# blocking.net
KiCad netlist of a schematic drawn in Altium Designer
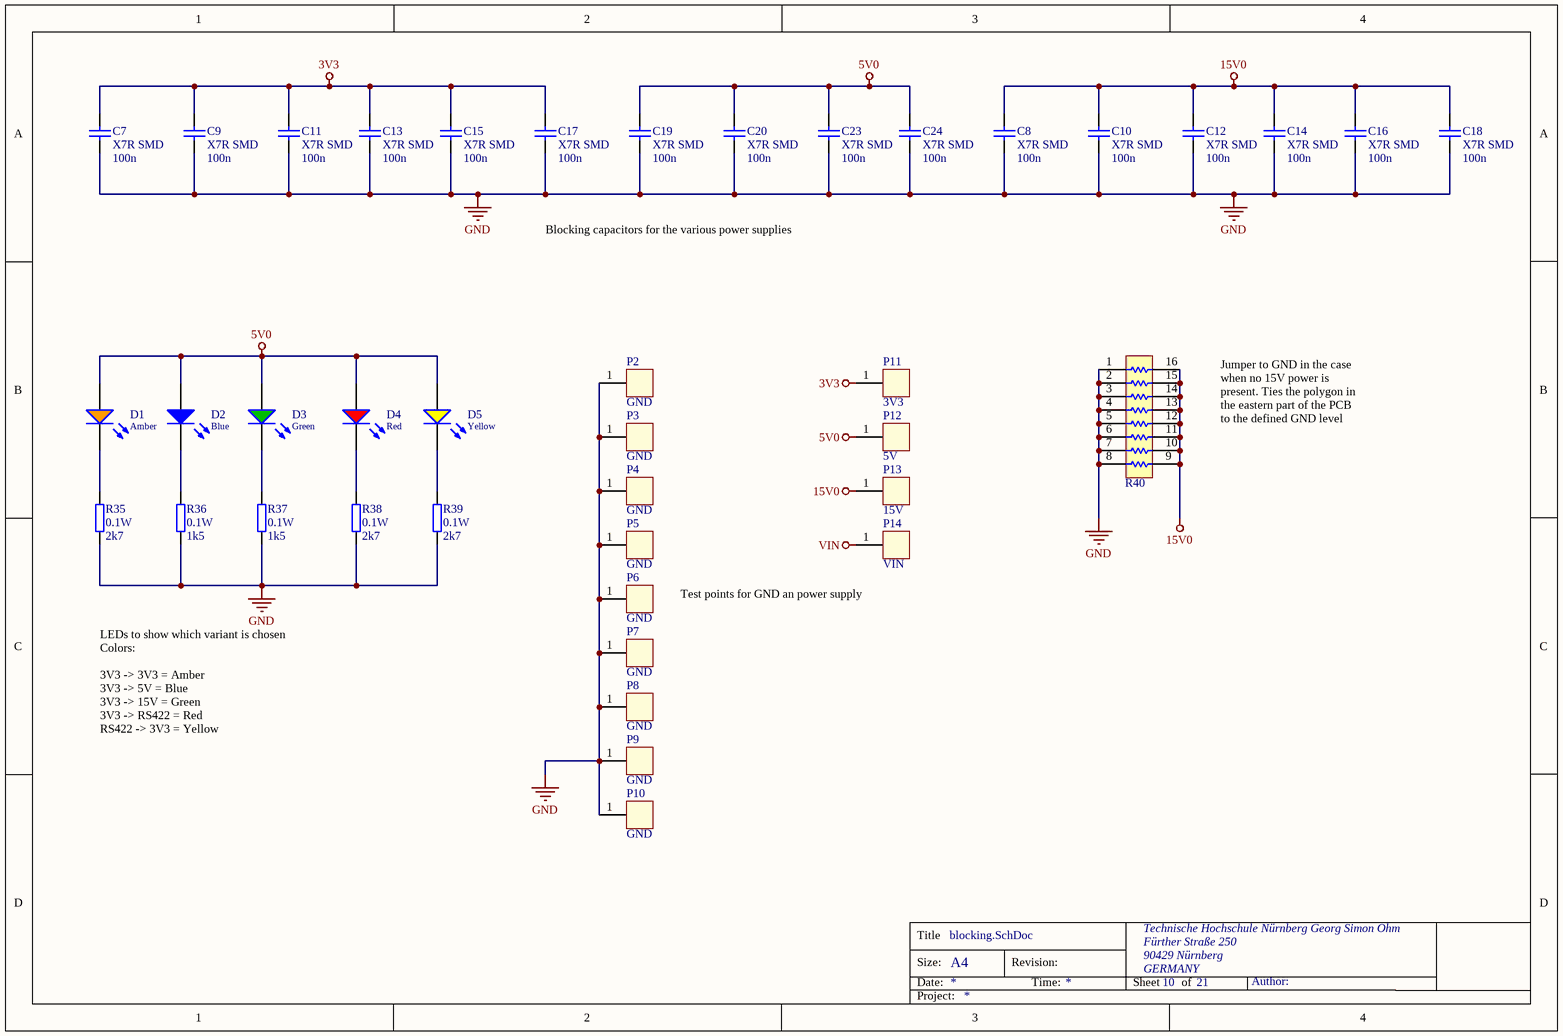
[diagram p0: blocking.SchDoc]

(export (version "E")
  (design (tool "Eeschema 10.0.6"))
  (components
    (comp (ref "C7")
      (value "X7R SMD")
      (footprint "CAPC3216X180X50ML20T25")
      (fields (field (name "ALTIUM_VALUE") "100n") (field (name "CREATED") "2019-12-08_Thilo_Wendt"))
      (libsource (lib "standard_rlc") (part "C_X7R_MEDIUM"))
    )
    (comp (ref "C8")
      (value "X7R SMD")
      (footprint "CAPC3216X180X50ML20T25")
      (fields (field (name "ALTIUM_VALUE") "100n") (field (name "CREATED") "2019-12-08_Thilo_Wendt"))
      (libsource (lib "standard_rlc") (part "C_X7R_MEDIUM"))
    )
    (comp (ref "C9")
      (value "X7R SMD")
      (footprint "CAPC3216X180X50ML20T25")
      (fields (field (name "ALTIUM_VALUE") "100n") (field (name "CREATED") "2019-12-08_Thilo_Wendt"))
      (libsource (lib "standard_rlc") (part "C_X7R_MEDIUM"))
    )
    (comp (ref "C10")
      (value "X7R SMD")
      (footprint "CAPC3216X180X50ML20T25")
      (fields (field (name "ALTIUM_VALUE") "100n") (field (name "CREATED") "2019-12-08_Thilo_Wendt"))
      (libsource (lib "standard_rlc") (part "C_X7R_MEDIUM"))
    )
    (comp (ref "C11")
      (value "X7R SMD")
      (footprint "CAPC3216X180X50ML20T25")
      (fields (field (name "ALTIUM_VALUE") "100n") (field (name "CREATED") "2019-12-08_Thilo_Wendt"))
      (libsource (lib "standard_rlc") (part "C_X7R_MEDIUM"))
    )
    (comp (ref "C12")
      (value "X7R SMD")
      (footprint "CAPC3216X180X50ML20T25")
      (fields (field (name "ALTIUM_VALUE") "100n") (field (name "CREATED") "2019-12-08_Thilo_Wendt"))
      (libsource (lib "standard_rlc") (part "C_X7R_MEDIUM"))
    )
    (comp (ref "C13")
      (value "X7R SMD")
      (footprint "CAPC3216X180X50ML20T25")
      (fields (field (name "ALTIUM_VALUE") "100n") (field (name "CREATED") "2019-12-08_Thilo_Wendt"))
      (libsource (lib "standard_rlc") (part "C_X7R_MEDIUM"))
    )
    (comp (ref "C14")
      (value "X7R SMD")
      (footprint "CAPC3216X180X50ML20T25")
      (fields (field (name "ALTIUM_VALUE") "100n") (field (name "CREATED") "2019-12-08_Thilo_Wendt"))
      (libsource (lib "standard_rlc") (part "C_X7R_MEDIUM"))
    )
    (comp (ref "C15")
      (value "X7R SMD")
      (footprint "CAPC3216X180X50ML20T25")
      (fields (field (name "ALTIUM_VALUE") "100n") (field (name "CREATED") "2019-12-08_Thilo_Wendt"))
      (libsource (lib "standard_rlc") (part "C_X7R_MEDIUM"))
    )
    (comp (ref "C16")
      (value "X7R SMD")
      (footprint "CAPC3216X180X50ML20T25")
      (fields (field (name "ALTIUM_VALUE") "100n") (field (name "CREATED") "2019-12-08_Thilo_Wendt"))
      (libsource (lib "standard_rlc") (part "C_X7R_MEDIUM"))
    )
    (comp (ref "C17")
      (value "X7R SMD")
      (footprint "CAPC3216X180X50ML20T25")
      (fields (field (name "ALTIUM_VALUE") "100n") (field (name "CREATED") "2019-12-08_Thilo_Wendt"))
      (libsource (lib "standard_rlc") (part "C_X7R_MEDIUM"))
    )
    (comp (ref "C18")
      (value "X7R SMD")
      (footprint "CAPC3216X180X50ML20T25")
      (fields (field (name "ALTIUM_VALUE") "100n") (field (name "CREATED") "2019-12-08_Thilo_Wendt"))
      (libsource (lib "standard_rlc") (part "C_X7R_MEDIUM"))
    )
    (comp (ref "C19")
      (value "X7R SMD")
      (footprint "CAPC3216X180X50ML20T25")
      (fields (field (name "ALTIUM_VALUE") "100n") (field (name "CREATED") "2019-12-08_Thilo_Wendt"))
      (libsource (lib "standard_rlc") (part "C_X7R_MEDIUM"))
    )
    (comp (ref "C20")
      (value "X7R SMD")
      (footprint "CAPC3216X180X50ML20T25")
      (fields (field (name "ALTIUM_VALUE") "100n") (field (name "CREATED") "2019-12-08_Thilo_Wendt"))
      (libsource (lib "standard_rlc") (part "C_X7R_MEDIUM"))
    )
    (comp (ref "C23")
      (value "X7R SMD")
      (footprint "CAPC3216X180X50ML20T25")
      (fields (field (name "ALTIUM_VALUE") "100n") (field (name "CREATED") "2019-12-08_Thilo_Wendt"))
      (libsource (lib "standard_rlc") (part "C_X7R_MEDIUM"))
    )
    (comp (ref "C24")
      (value "X7R SMD")
      (footprint "CAPC3216X180X50ML20T25")
      (fields (field (name "ALTIUM_VALUE") "100n") (field (name "CREATED") "2019-12-08_Thilo_Wendt"))
      (libsource (lib "standard_rlc") (part "C_X7R_MEDIUM"))
    )
    (comp (ref "D1")
      (value "Amber")
      (footprint "WL-SMCW_0603")
      (description "WL-SMCW SMD Mono-color Chip LED Waterclear, size 0603, Red, 2 V, 140°")
      (fields (field (name "EMITTING COLOR") "Amber") (field (name "CREATED") "2020-01-07_Thilo_Wendt"))
      (libsource (lib "optoelectronics") (part "LED_Amber"))
    )
    (comp (ref "D2")
      (value "Blue")
      (footprint "WL-SMCW_0603")
      (description "WL-SMCW SMD Mono-color Chip LED Waterclear, size 0603, Blue, 3.2 V, 140°")
      (fields
        (field (name "MPN") "150060BS75000")
        (field (name "MF") "Wuerth Elektronik")
        (field (name "EMITTING COLOR") "Blue")
        (field (name "CREATED") "2018_09_06_AGeiger")
      )
      (libsource (lib "optoelectronics") (part "LED_Blue"))
    )
    (comp (ref "D3")
      (value "Green")
      (footprint "WL-SMCW_0603")
      (description "WL-SMCW SMD Mono-color Chip LED Waterclear, size 0603, Green, 3.2 V, 140°")
      (fields
        (field (name "MPN") "150060GS75000")
        (field (name "MF") "Wuerth Elektronik")
        (field (name "EMITTING COLOR") "Green")
        (field (name "CREATED") "2018_09_06_AGeiger")
      )
      (libsource (lib "optoelectronics") (part "LED_Green"))
    )
    (comp (ref "D4")
      (value "Red")
      (footprint "WL-SMCW_0603")
      (description "WL-SMCW SMD Mono-color Chip LED Waterclear, size 0603, Red, 2 V, 140°")
      (fields
        (field (name "MPN") "150060RS75000")
        (field (name "MF") "Wuerth Elektronik")
        (field (name "EMITTING COLOR") "Red")
        (field (name "CREATED") "2018_09_06_AGeiger")
      )
      (libsource (lib "optoelectronics") (part "LED_Red"))
    )
    (comp (ref "D5")
      (value "Yellow")
      (footprint "WL-SMCW_0603")
      (description "WL-SMCW SMD Mono-color Chip LED Waterclear, size 0603, Red, 2 V, 140°")
      (fields (field (name "EMITTING COLOR") "Yellow") (field (name "CREATED") "2020-01-07_Thilo_Wendt"))
      (libsource (lib "optoelectronics") (part "LED_Yellow"))
    )
    (comp (ref "P2")
      (value "GND")
      (footprint "PinHeader1")
      (description "Pin Header with 1 terminal")
      (fields (field (name "CREATED") "2020-01-08_Thilo_Wendt"))
      (libsource (lib "connectors") (part "PinHeader1"))
    )
    (comp (ref "P3")
      (value "GND")
      (footprint "PinHeader1")
      (description "Pin Header with 1 terminal")
      (fields (field (name "CREATED") "2020-01-08_Thilo_Wendt"))
      (libsource (lib "connectors") (part "PinHeader1"))
    )
    (comp (ref "P4")
      (value "GND")
      (footprint "PinHeader1")
      (description "Pin Header with 1 terminal")
      (fields (field (name "CREATED") "2020-01-08_Thilo_Wendt"))
      (libsource (lib "connectors") (part "PinHeader1"))
    )
    (comp (ref "P5")
      (value "GND")
      (footprint "PinHeader1")
      (description "Pin Header with 1 terminal")
      (fields (field (name "CREATED") "2020-01-08_Thilo_Wendt"))
      (libsource (lib "connectors") (part "PinHeader1"))
    )
    (comp (ref "P6")
      (value "GND")
      (footprint "PinHeader1")
      (description "Pin Header with 1 terminal")
      (fields (field (name "CREATED") "2020-01-08_Thilo_Wendt"))
      (libsource (lib "connectors") (part "PinHeader1"))
    )
    (comp (ref "P7")
      (value "GND")
      (footprint "PinHeader1")
      (description "Pin Header with 1 terminal")
      (fields (field (name "CREATED") "2020-01-08_Thilo_Wendt"))
      (libsource (lib "connectors") (part "PinHeader1"))
    )
    (comp (ref "P8")
      (value "GND")
      (footprint "PinHeader1")
      (description "Pin Header with 1 terminal")
      (fields (field (name "CREATED") "2020-01-08_Thilo_Wendt"))
      (libsource (lib "connectors") (part "PinHeader1"))
    )
    (comp (ref "P9")
      (value "GND")
      (footprint "PinHeader1")
      (description "Pin Header with 1 terminal")
      (fields (field (name "CREATED") "2020-01-08_Thilo_Wendt"))
      (libsource (lib "connectors") (part "PinHeader1"))
    )
    (comp (ref "P10")
      (value "GND")
      (footprint "PinHeader1")
      (description "Pin Header with 1 terminal")
      (fields (field (name "CREATED") "2020-01-08_Thilo_Wendt"))
      (libsource (lib "connectors") (part "PinHeader1"))
    )
    (comp (ref "P11")
      (value "3V3")
      (footprint "PinHeader1")
      (description "Pin Header with 1 terminal")
      (fields (field (name "CREATED") "2020-01-08_Thilo_Wendt"))
      (libsource (lib "connectors") (part "PinHeader1"))
    )
    (comp (ref "P12")
      (value "5V")
      (footprint "PinHeader1")
      (description "Pin Header with 1 terminal")
      (fields (field (name "CREATED") "2020-01-08_Thilo_Wendt"))
      (libsource (lib "connectors") (part "PinHeader1"))
    )
    (comp (ref "P13")
      (value "15V")
      (footprint "PinHeader1")
      (description "Pin Header with 1 terminal")
      (fields (field (name "CREATED") "2020-01-08_Thilo_Wendt"))
      (libsource (lib "connectors") (part "PinHeader1"))
    )
    (comp (ref "P14")
      (value "VIN")
      (footprint "PinHeader1")
      (description "Pin Header with 1 terminal")
      (fields (field (name "CREATED") "2020-01-08_Thilo_Wendt"))
      (libsource (lib "connectors") (part "PinHeader1"))
    )
    (comp (ref "R35")
      (value "0.1W")
      (footprint "RESC1608X55X30NL15T15")
      (description "Standard thick film resistor")
      (fields (field (name "ALTIUM_VALUE") "2k7") (field (name "CREATED") "2019-12-08_Thilo_Wendt"))
      (libsource (lib "standard_rlc") (part "R_0.1W_SMD"))
    )
    (comp (ref "R36")
      (value "0.1W")
      (footprint "RESC1608X55X30NL15T15")
      (description "Standard thick film resistor")
      (fields (field (name "ALTIUM_VALUE") "1k5") (field (name "CREATED") "2019-12-08_Thilo_Wendt"))
      (libsource (lib "standard_rlc") (part "R_0.1W_SMD"))
    )
    (comp (ref "R37")
      (value "0.1W")
      (footprint "RESC1608X55X30NL15T15")
      (description "Standard thick film resistor")
      (fields (field (name "ALTIUM_VALUE") "1k5") (field (name "CREATED") "2019-12-08_Thilo_Wendt"))
      (libsource (lib "standard_rlc") (part "R_0.1W_SMD"))
    )
    (comp (ref "R38")
      (value "0.1W")
      (footprint "RESC1608X55X30NL15T15")
      (description "Standard thick film resistor")
      (fields (field (name "ALTIUM_VALUE") "2k7") (field (name "CREATED") "2019-12-08_Thilo_Wendt"))
      (libsource (lib "standard_rlc") (part "R_0.1W_SMD"))
    )
    (comp (ref "R39")
      (value "0.1W")
      (footprint "RESC1608X55X30NL15T15")
      (description "Standard thick film resistor")
      (fields (field (name "ALTIUM_VALUE") "2k7") (field (name "CREATED") "2019-12-08_Thilo_Wendt"))
      (libsource (lib "standard_rlc") (part "R_0.1W_SMD"))
    )
    (comp (ref "R40")
      (value "0.063W")
      (footprint "RESCAXE-50P380X160X45-16N")
      (description "Standard thick film resistor array with 8 resistors")
      (fields (field (name "CREATED") "2020-01-03_Thilo_Wendt"))
      (libsource (lib "standard_rlc") (part "8xR-Array_1_part"))
    )
  )
  (nets
    (net (code "1") (name "3V3") (class "Default")
      (node (ref "C11") (pin "2") (pinfunction "2_2") (pintype "passive"))
      (node (ref "C13") (pin "2") (pinfunction "2_2") (pintype "passive"))
      (node (ref "C15") (pin "2") (pinfunction "2_2") (pintype "passive"))
      (node (ref "C17") (pin "2") (pinfunction "2_2") (pintype "passive"))
      (node (ref "C7") (pin "2") (pinfunction "2_2") (pintype "passive"))
      (node (ref "C9") (pin "2") (pinfunction "2_2") (pintype "passive"))
      (node (ref "P11") (pin "1") (pinfunction "1_1") (pintype "passive"))
    )
    (net (code "2") (name "5V0") (class "Default")
      (node (ref "C19") (pin "2") (pinfunction "2_2") (pintype "passive"))
      (node (ref "C20") (pin "2") (pinfunction "2_2") (pintype "passive"))
      (node (ref "C23") (pin "2") (pinfunction "2_2") (pintype "passive"))
      (node (ref "C24") (pin "2") (pinfunction "2_2") (pintype "passive"))
      (node (ref "D1") (pin "2") (pinfunction "A_2") (pintype "passive"))
      (node (ref "D2") (pin "2") (pinfunction "A_2") (pintype "passive"))
      (node (ref "D3") (pin "2") (pinfunction "A_2") (pintype "passive"))
      (node (ref "D4") (pin "2") (pinfunction "A_2") (pintype "passive"))
      (node (ref "D5") (pin "2") (pinfunction "A_2") (pintype "passive"))
      (node (ref "P12") (pin "1") (pinfunction "1_1") (pintype "passive"))
    )
    (net (code "3") (name "15V0") (class "Default")
      (node (ref "C10") (pin "2") (pinfunction "2_2") (pintype "passive"))
      (node (ref "C12") (pin "2") (pinfunction "2_2") (pintype "passive"))
      (node (ref "C14") (pin "2") (pinfunction "2_2") (pintype "passive"))
      (node (ref "C16") (pin "2") (pinfunction "2_2") (pintype "passive"))
      (node (ref "C18") (pin "2") (pinfunction "2_2") (pintype "passive"))
      (node (ref "C8") (pin "2") (pinfunction "2_2") (pintype "passive"))
      (node (ref "P13") (pin "1") (pinfunction "1_1") (pintype "passive"))
      (node (ref "R40") (pin "10") (pinfunction "10_10") (pintype "passive"))
      (node (ref "R40") (pin "11") (pinfunction "11_11") (pintype "passive"))
      (node (ref "R40") (pin "12") (pinfunction "12_12") (pintype "passive"))
      (node (ref "R40") (pin "13") (pinfunction "13_13") (pintype "passive"))
      (node (ref "R40") (pin "14") (pinfunction "14_14") (pintype "passive"))
      (node (ref "R40") (pin "15") (pinfunction "15_15") (pintype "passive"))
      (node (ref "R40") (pin "16") (pinfunction "16_16") (pintype "passive"))
      (node (ref "R40") (pin "9") (pinfunction "9_9") (pintype "passive"))
    )
    (net (code "4") (name "GND") (class "Default")
      (node (ref "C10") (pin "1") (pinfunction "1_1") (pintype "passive"))
      (node (ref "C11") (pin "1") (pinfunction "1_1") (pintype "passive"))
      (node (ref "C12") (pin "1") (pinfunction "1_1") (pintype "passive"))
      (node (ref "C13") (pin "1") (pinfunction "1_1") (pintype "passive"))
      (node (ref "C14") (pin "1") (pinfunction "1_1") (pintype "passive"))
      (node (ref "C15") (pin "1") (pinfunction "1_1") (pintype "passive"))
      (node (ref "C16") (pin "1") (pinfunction "1_1") (pintype "passive"))
      (node (ref "C17") (pin "1") (pinfunction "1_1") (pintype "passive"))
      (node (ref "C18") (pin "1") (pinfunction "1_1") (pintype "passive"))
      (node (ref "C19") (pin "1") (pinfunction "1_1") (pintype "passive"))
      (node (ref "C20") (pin "1") (pinfunction "1_1") (pintype "passive"))
      (node (ref "C23") (pin "1") (pinfunction "1_1") (pintype "passive"))
      (node (ref "C24") (pin "1") (pinfunction "1_1") (pintype "passive"))
      (node (ref "C7") (pin "1") (pinfunction "1_1") (pintype "passive"))
      (node (ref "C8") (pin "1") (pinfunction "1_1") (pintype "passive"))
      (node (ref "C9") (pin "1") (pinfunction "1_1") (pintype "passive"))
      (node (ref "P10") (pin "1") (pinfunction "1_1") (pintype "passive"))
      (node (ref "P2") (pin "1") (pinfunction "1_1") (pintype "passive"))
      (node (ref "P3") (pin "1") (pinfunction "1_1") (pintype "passive"))
      (node (ref "P4") (pin "1") (pinfunction "1_1") (pintype "passive"))
      (node (ref "P5") (pin "1") (pinfunction "1_1") (pintype "passive"))
      (node (ref "P6") (pin "1") (pinfunction "1_1") (pintype "passive"))
      (node (ref "P7") (pin "1") (pinfunction "1_1") (pintype "passive"))
      (node (ref "P8") (pin "1") (pinfunction "1_1") (pintype "passive"))
      (node (ref "P9") (pin "1") (pinfunction "1_1") (pintype "passive"))
      (node (ref "R35") (pin "2") (pinfunction "2_2") (pintype "passive"))
      (node (ref "R36") (pin "2") (pinfunction "2_2") (pintype "passive"))
      (node (ref "R37") (pin "2") (pinfunction "2_2") (pintype "passive"))
      (node (ref "R38") (pin "2") (pinfunction "2_2") (pintype "passive"))
      (node (ref "R39") (pin "2") (pinfunction "2_2") (pintype "passive"))
      (node (ref "R40") (pin "1") (pinfunction "1_1") (pintype "passive"))
      (node (ref "R40") (pin "2") (pinfunction "2_2") (pintype "passive"))
      (node (ref "R40") (pin "3") (pinfunction "3_3") (pintype "passive"))
      (node (ref "R40") (pin "4") (pinfunction "4_4") (pintype "passive"))
      (node (ref "R40") (pin "5") (pinfunction "5_5") (pintype "passive"))
      (node (ref "R40") (pin "6") (pinfunction "6_6") (pintype "passive"))
      (node (ref "R40") (pin "7") (pinfunction "7_7") (pintype "passive"))
      (node (ref "R40") (pin "8") (pinfunction "8_8") (pintype "passive"))
    )
    (net (code "5") (name "Net-(D1-K)") (class "Default")
      (node (ref "D1") (pin "1") (pinfunction "K_1") (pintype "passive"))
      (node (ref "R35") (pin "1") (pinfunction "1_1") (pintype "passive"))
    )
    (net (code "6") (name "Net-(D2-K)") (class "Default")
      (node (ref "D2") (pin "1") (pinfunction "K_1") (pintype "passive"))
      (node (ref "R36") (pin "1") (pinfunction "1_1") (pintype "passive"))
    )
    (net (code "7") (name "Net-(D3-K)") (class "Default")
      (node (ref "D3") (pin "1") (pinfunction "K_1") (pintype "passive"))
      (node (ref "R37") (pin "1") (pinfunction "1_1") (pintype "passive"))
    )
    (net (code "8") (name "Net-(D4-K)") (class "Default")
      (node (ref "D4") (pin "1") (pinfunction "K_1") (pintype "passive"))
      (node (ref "R38") (pin "1") (pinfunction "1_1") (pintype "passive"))
    )
    (net (code "9") (name "Net-(D5-K)") (class "Default")
      (node (ref "D5") (pin "1") (pinfunction "K_1") (pintype "passive"))
      (node (ref "R39") (pin "1") (pinfunction "1_1") (pintype "passive"))
    )
    (net (code "10") (name "VIN") (class "Default")
      (node (ref "P14") (pin "1") (pinfunction "1_1") (pintype "passive"))
    )
  )
)
